# USB.net
KiCad netlist of a schematic drawn in Altium Designer
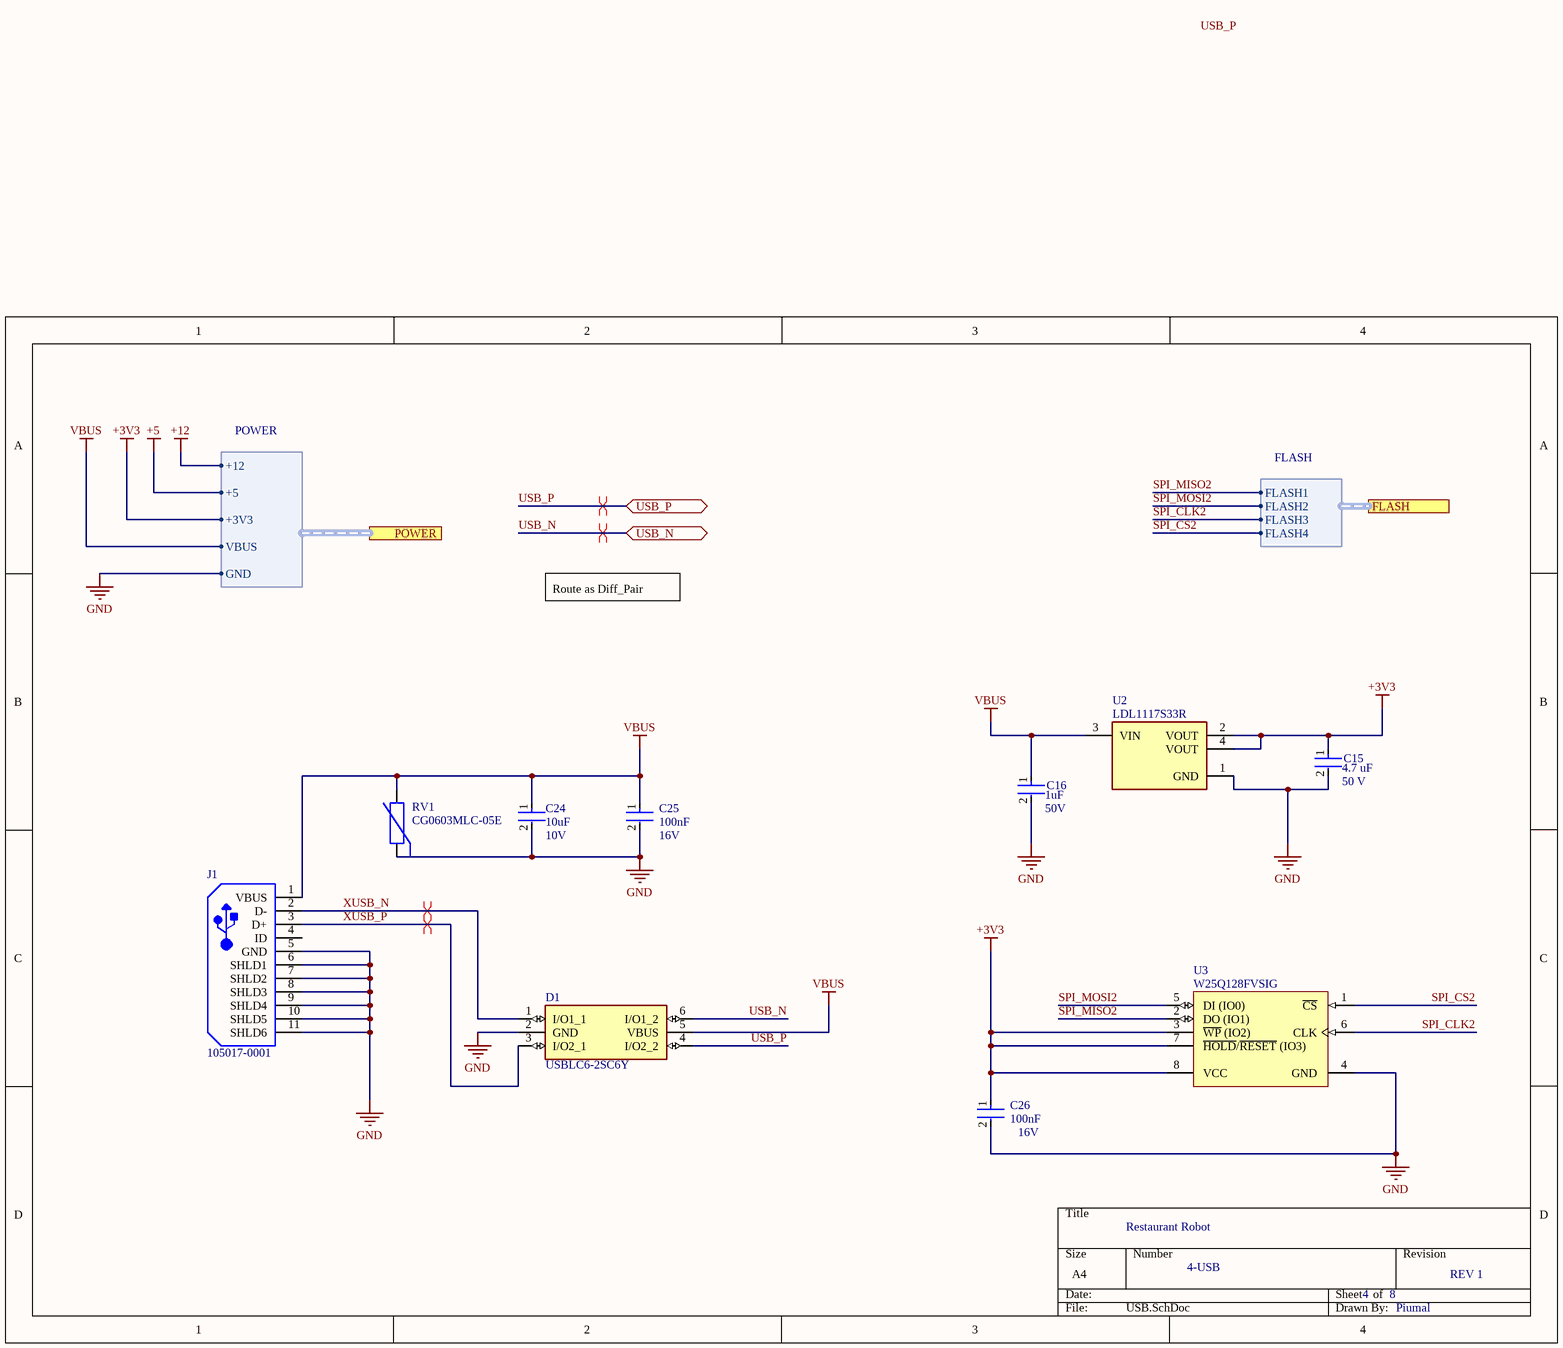
[diagram p0: USB.SchDoc]

(export (version "E")
  (design (tool "Eeschema 10.0.6"))
  (components
    (comp (ref "C15")
      (value "CC1206KKX7R9BB475")
      (footprint "FP-CC1206-1_25-MFG")
      (description "CAP CER 4.7UF 50V X7R 1206")
      (fields
        (field (name "VOLTAGE RATING") "50 V")
        (field (name "TOLERANCE") "0.1")
        (field (name "CAPACITANCE") "4.7 uF")
        (field (name "MANUFACTURER") "Yageo")
      )
      (libsource (lib "Altium Content Vault") (part "11868f565c42a9108669ba33697ecf6"))
    )
    (comp (ref "C16")
      (value "12065C105KAT2A")
      (footprint "FP-1206-L_3_2_0_2-W_1_6_0-IPC_A")
      (description "General Purpose Ceramic Capacitor, 1206, 1uF, 10%, X7R, 15%, 50V")
      (fields
        (field (name "VOLTAGE RATING") "50V")
        (field (name "CAPACITANCE") "1uF")
        (field (name "TOLERANCE") "10%")
        (field (name "VOLTAGE") "25V")
      )
      (libsource (lib "Altium Content Vault") (part "b4654b650e69147ec39a6b967a45e02"))
    )
    (comp (ref "C24")
      (value "1206ZD106KAT2A")
      (footprint "FP-1206-L_3_2_0_2-W_1_6_0-IPC_A")
      (description "General Purpose Ceramic Capacitor, 1206, 10uF, 10%, X5R, 15%, 10V")
      (fields
        (field (name "TOLERANCE") "10%")
        (field (name "VOLTAGE") "10V")
        (field (name "CAPACITANCE") "10uF")
      )
      (libsource (lib "Altium Content Vault") (part "02cd4be3c70576c341d710602a673aa"))
    )
    (comp (ref "C25")
      (value "CL21B104KOANNNC")
      (footprint "FP-CL21-IPC_A")
      (description "CL21 Series 0805 100nF 16V ±10% Tolerance X7R Multilayer Ceramic Chip Capacitor")
      (fields
        (field (name "VOLTAGE RATING (DC)") "16V")
        (field (name "TOLERANCE") "10%")
        (field (name "CAPACITANCE") "100nF")
      )
      (libsource (lib "Altium Content Vault") (part "b4654b650e69147ec39a6b967a45e02"))
    )
    (comp (ref "C26")
      (value "CL21B104KOANNNC")
      (footprint "FP-CL21-IPC_A")
      (description "CL21 Series 0805 100nF 16V ±10% Tolerance X7R Multilayer Ceramic Chip Capacitor")
      (fields
        (field (name "VOLTAGE RATING (DC)") "16V")
        (field (name "TOLERANCE") "10%")
        (field (name "CAPACITANCE") "100nF")
      )
      (libsource (lib "Altium Content Vault") (part "b4654b650e69147ec39a6b967a45e02"))
    )
    (comp (ref "D1")
      (value "USBLC6-2SC6Y")
      (footprint "SOT95P280X145-6N")
      (description "17V Clamp 5A (8/20µs) Ipp Tvs Diode Surface Mount SOT-23-6")
      (fields (field (name "MF") "STMicroelectronics"))
      (libsource (lib "USBLC6-2SC6Y") (part "USBLC6-2SC6Y"))
    )
    (comp (ref "J1")
      (value "105017-0001")
      (footprint "USB-MICRO-B_V")
      (fields (field (name "MANUFACTURER") "Molex"))
      (libsource (lib "Altium Content Vault") (part "USB-5-6SHLD"))
    )
    (comp (ref "RV1")
      (value "CG0603MLC-05E")
      (footprint "BOUR-CG0603-2_V")
      (description "ESD Protector, 5 V Supply, -40 to 85 degC, 1.6 x 0.8 x 0.55 mm SMD, RoHS, Tape and Reel")
      (fields (field (name "MANUFACTURER") "Bourns"))
      (libsource (lib "Altium Content Vault") (part "BOUR-VSR-2"))
    )
    (comp (ref "U2")
      (value "LDL1117S33R")
      (footprint "FP-SOT223-0046067-IPC_C")
      (description "IC REG LINEAR 3.3V 1.2A SOT223")
      (fields
        (field (name "OCTOPART") "https://octopart.com/ldl1117s33r-stmicroelectronics-81876163")
        (field (name "MANUFACTURER") "STMicroelectronics")
      )
      (libsource (lib "Altium Content Vault") (part "a602d55cb6d43002de8a72f1c695f0a"))
    )
    (comp (ref "U3")
      (value "W25Q128FVSIG")
      (footprint "WINB-SOIC-8_M")
      (fields (field (name "MANUFACTURER") "Winbond"))
      (libsource (lib "Altium Content Vault") (part "WINB-W25Q128FVSIG-SOIC-8"))
    )
  )
  (nets
    (net (code "3") (name "+3V3") (class "Default")
      (node (ref "C15") (pin "1") (pinfunction "1_1") (pintype "passive"))
      (node (ref "C26") (pin "1") (pinfunction "1_1") (pintype "passive"))
      (node (ref "U2") (pin "2") (pinfunction "VOUT_2") (pintype "passive"))
      (node (ref "U2") (pin "4") (pinfunction "VOUT_4") (pintype "passive"))
      (node (ref "U3") (pin "3") (pinfunction "~{WP}_(IO2)_3") (pintype "passive"))
      (node (ref "U3") (pin "7") (pinfunction "~{HOLD}/~{RESET}_(IO3)_7") (pintype "passive"))
      (node (ref "U3") (pin "8") (pinfunction "VCC_8") (pintype "passive"))
    )
    (net (code "6") (name "/SPI_CLK2") (class "Default")
      (node (ref "U3") (pin "6") (pinfunction "CLK_6") (pintype "input"))
    )
    (net (code "7") (name "/SPI_CS2") (class "Default")
      (node (ref "U3") (pin "1") (pinfunction "~{CS}_1") (pintype "input"))
    )
    (net (code "8") (name "/SPI_MISO2") (class "Default")
      (node (ref "U3") (pin "2") (pinfunction "DO_(IO1)_2") (pintype "bidirectional"))
    )
    (net (code "9") (name "/SPI_MOSI2") (class "Default")
      (node (ref "U3") (pin "5") (pinfunction "DI_(IO0)_5") (pintype "bidirectional"))
    )
    (net (code "10") (name "/USB_N") (class "Default")
      (node (ref "D1") (pin "6") (pinfunction "I/O1_2_6") (pintype "bidirectional"))
    )
    (net (code "11") (name "/USB_P") (class "Default")
      (node (ref "D1") (pin "4") (pinfunction "I/O2_2_4") (pintype "bidirectional"))
    )
    (net (code "12") (name "/XUSB_N") (class "Default")
      (node (ref "D1") (pin "1") (pinfunction "I/O1_1_1") (pintype "bidirectional"))
      (node (ref "J1") (pin "2") (pinfunction "D-_2") (pintype "passive"))
    )
    (net (code "13") (name "/XUSB_P") (class "Default")
      (node (ref "D1") (pin "3") (pinfunction "I/O2_1_3") (pintype "bidirectional"))
      (node (ref "J1") (pin "3") (pinfunction "D+_3") (pintype "passive"))
    )
    (net (code "16") (name "GND") (class "Default")
      (node (ref "C15") (pin "2") (pinfunction "2_2") (pintype "passive"))
      (node (ref "C16") (pin "2") (pinfunction "2_2") (pintype "passive"))
      (node (ref "C24") (pin "2") (pinfunction "2_2") (pintype "passive"))
      (node (ref "C25") (pin "2") (pinfunction "2_2") (pintype "passive"))
      (node (ref "C26") (pin "2") (pinfunction "2_2") (pintype "passive"))
      (node (ref "D1") (pin "2") (pinfunction "GND_2") (pintype "passive"))
      (node (ref "J1") (pin "10") (pinfunction "SHLD5_10") (pintype "passive"))
      (node (ref "J1") (pin "11") (pinfunction "SHLD6_11") (pintype "passive"))
      (node (ref "J1") (pin "5") (pinfunction "GND_5") (pintype "passive"))
      (node (ref "J1") (pin "6") (pinfunction "SHLD1_6") (pintype "passive"))
      (node (ref "J1") (pin "7") (pinfunction "SHLD2_7") (pintype "passive"))
      (node (ref "J1") (pin "8") (pinfunction "SHLD3_8") (pintype "passive"))
      (node (ref "J1") (pin "9") (pinfunction "SHLD4_9") (pintype "passive"))
      (node (ref "RV1") (pin "1") (pinfunction "1_1") (pintype "passive"))
      (node (ref "U2") (pin "1") (pinfunction "GND_1") (pintype "power_in"))
      (node (ref "U3") (pin "4") (pinfunction "GND_4") (pintype "power_in"))
    )
    (net (code "17") (name "VBUS") (class "Default")
      (node (ref "C16") (pin "1") (pinfunction "1_1") (pintype "passive"))
      (node (ref "C24") (pin "1") (pinfunction "1_1") (pintype "passive"))
      (node (ref "C25") (pin "1") (pinfunction "1_1") (pintype "passive"))
      (node (ref "D1") (pin "5") (pinfunction "VBUS_5") (pintype "power_in"))
      (node (ref "J1") (pin "1") (pinfunction "VBUS_1") (pintype "passive"))
      (node (ref "RV1") (pin "2") (pinfunction "2_2") (pintype "passive"))
      (node (ref "U2") (pin "3") (pinfunction "VIN_3") (pintype "power_in"))
    )
    (net (code "18") (name "unconnected-(J1-ID-Pad4)") (class "Default")
      (node (ref "J1") (pin "4") (pinfunction "ID_4") (pintype "passive"))
    )
  )
)
